# W040B.net
KiCad netlist of a schematic drawn in EAGLE
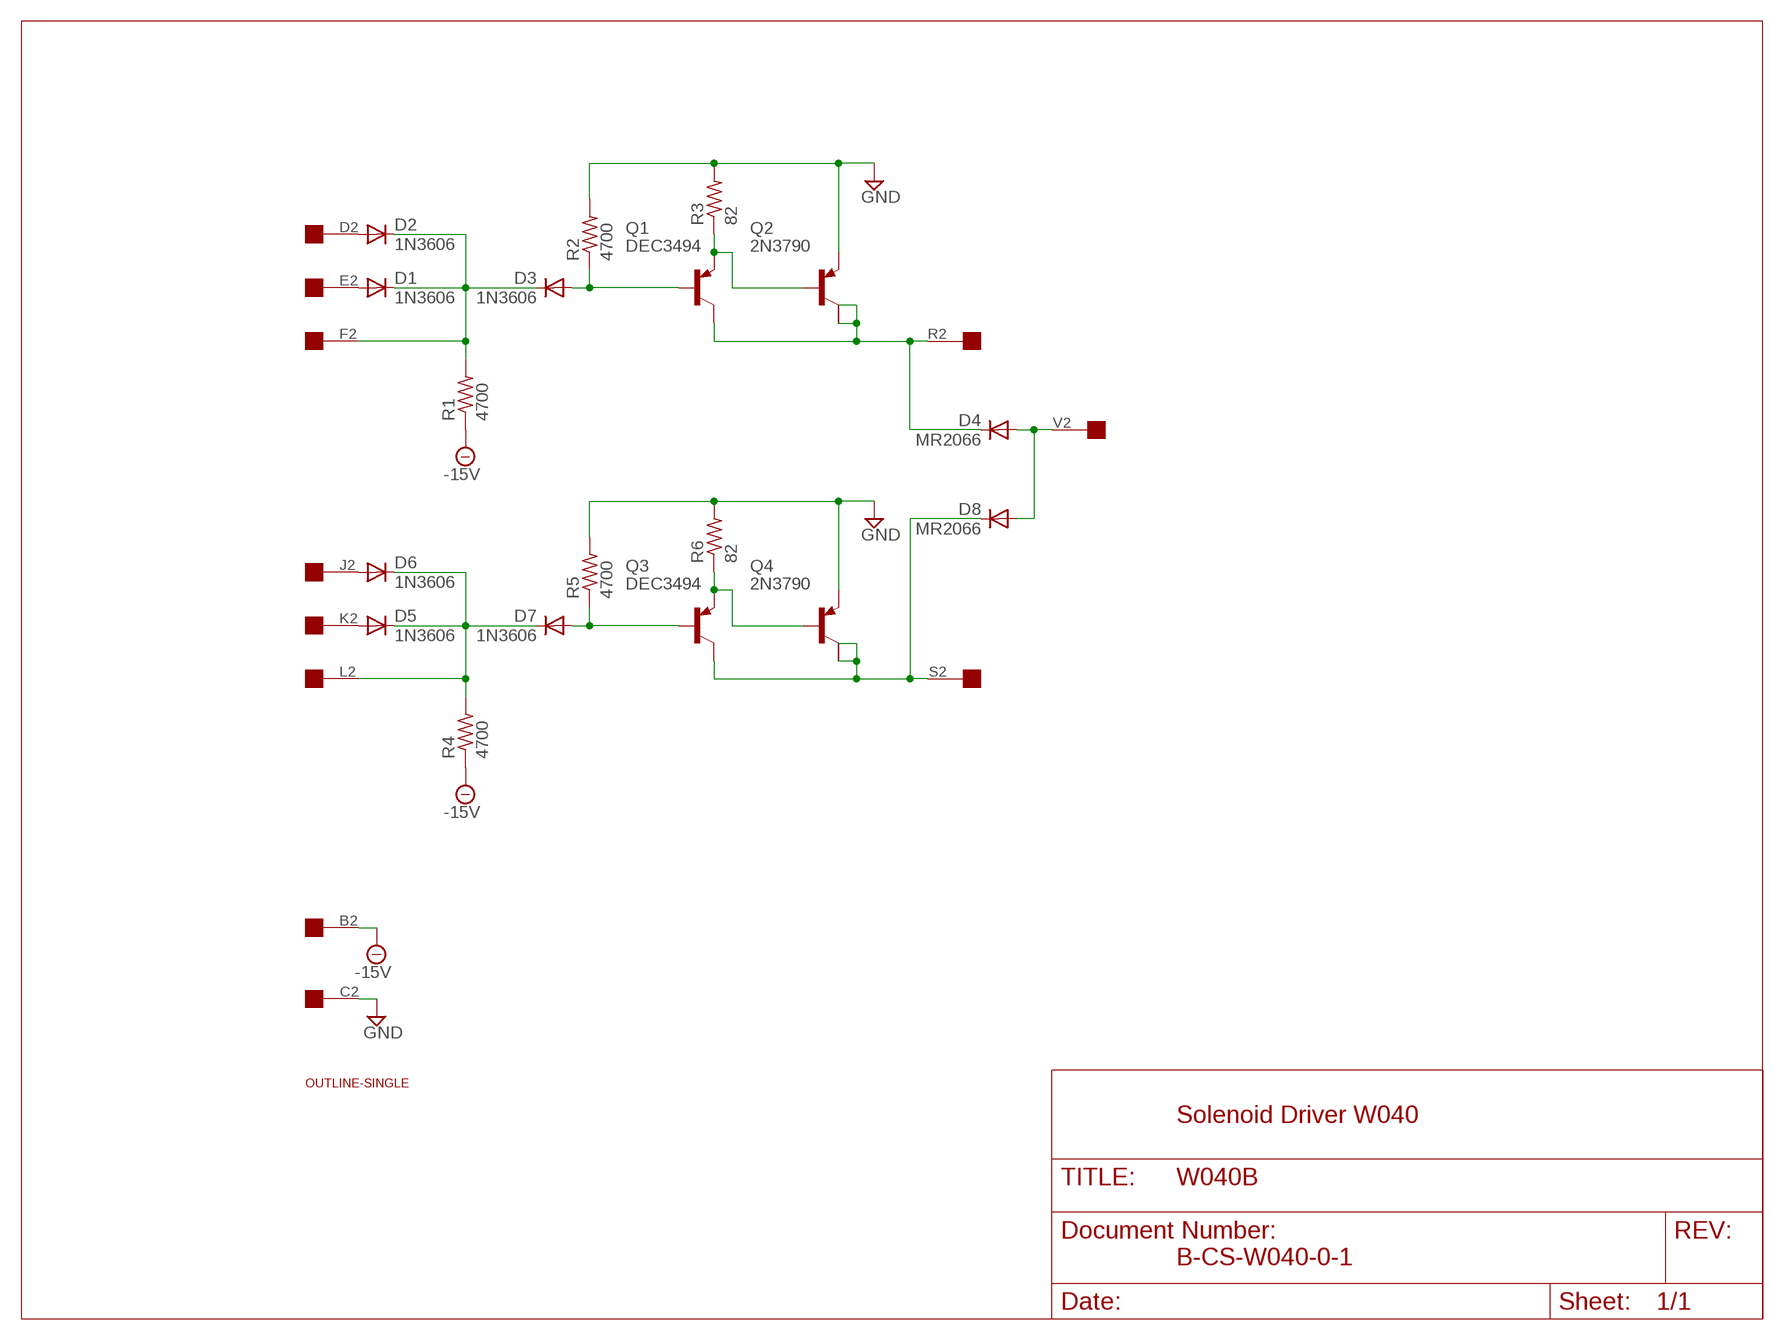
[diagram p0: schematic, sheet 1]

(export (version "E")
  (design (tool "Eeschema 10.0.6"))
  (components
    (comp (ref "D1")
      (value "1N3606")
      (footprint "eagle-import:DO35-10")
      (libsource (lib "eagle-import") (part "1N4148"))
    )
    (comp (ref "D2")
      (value "1N3606")
      (footprint "eagle-import:DO35-10")
      (libsource (lib "eagle-import") (part "1N4148"))
    )
    (comp (ref "D3")
      (value "1N3606")
      (footprint "eagle-import:DO35-10")
      (libsource (lib "eagle-import") (part "1N4148"))
    )
    (comp (ref "D4")
      (value "MR2066")
      (footprint "eagle-import:DO41-10")
      (libsource (lib "eagle-import") (part "1N4004"))
    )
    (comp (ref "D5")
      (value "1N3606")
      (footprint "eagle-import:DO35-10")
      (libsource (lib "eagle-import") (part "1N4148"))
    )
    (comp (ref "D6")
      (value "1N3606")
      (footprint "eagle-import:DO35-10")
      (libsource (lib "eagle-import") (part "1N4148"))
    )
    (comp (ref "D7")
      (value "1N3606")
      (footprint "eagle-import:DO35-10")
      (libsource (lib "eagle-import") (part "1N4148"))
    )
    (comp (ref "D8")
      (value "MR2066")
      (footprint "eagle-import:DO41-10")
      (libsource (lib "eagle-import") (part "1N4004"))
    )
    (comp (ref "Q1")
      (value "DEC3494")
      (footprint "eagle-import:TO39")
      (libsource (lib "eagle-import") (part "2N2904"))
    )
    (comp (ref "Q2")
      (value "2N3790")
      (footprint "eagle-import:TO3")
      (libsource (lib "eagle-import") (part "2N4902"))
    )
    (comp (ref "Q3")
      (value "DEC3494")
      (footprint "eagle-import:TO39")
      (libsource (lib "eagle-import") (part "2N2904"))
    )
    (comp (ref "Q4")
      (value "2N3790")
      (footprint "eagle-import:TO3")
      (libsource (lib "eagle-import") (part "2N4902"))
    )
    (comp (ref "R1")
      (value "4700")
      (footprint "eagle-import:0207_10")
      (libsource (lib "eagle-import") (part "R-US_0207/10"))
    )
    (comp (ref "R2")
      (value "4700")
      (footprint "eagle-import:0207_10")
      (libsource (lib "eagle-import") (part "R-US_0207/10"))
    )
    (comp (ref "R3")
      (value "82")
      (footprint "eagle-import:0207_10")
      (libsource (lib "eagle-import") (part "R-US_0207/10"))
    )
    (comp (ref "R4")
      (value "4700")
      (footprint "eagle-import:0207_10")
      (libsource (lib "eagle-import") (part "R-US_0207/10"))
    )
    (comp (ref "R5")
      (value "4700")
      (footprint "eagle-import:0207_10")
      (libsource (lib "eagle-import") (part "R-US_0207/10"))
    )
    (comp (ref "R6")
      (value "82")
      (footprint "eagle-import:0207_10")
      (libsource (lib "eagle-import") (part "R-US_0207/10"))
    )
    (comp (ref "U$1")
      (value "OUTLINE-SINGLE")
      (footprint "eagle-import:SINGLE")
      (libsource (lib "eagle-import") (part "OUTLINE-SINGLE"))
    )
    (comp (ref "U$2")
      (value "EDGE-1")
      (footprint "eagle-import:EDGE-CON1")
      (libsource (lib "eagle-import") (part "EDGE-1"))
    )
  )
  (nets
    (net (code "1") (name "-15V") (class "Default")
      (node (ref "R1") (pin "1") (pinfunction "1_1") (pintype "passive"))
      (node (ref "R4") (pin "1") (pinfunction "1_1") (pintype "passive"))
      (node (ref "U$2") (pin "B2") (pinfunction "1_B2") (pintype "bidirectional"))
    )
    (net (code "2") (name "GND") (class "Default")
      (node (ref "Q2") (pin "E") (pinfunction "E_E") (pintype "passive"))
      (node (ref "Q4") (pin "E") (pinfunction "E_E") (pintype "passive"))
      (node (ref "R2") (pin "2") (pinfunction "2_2") (pintype "passive"))
      (node (ref "R3") (pin "2") (pinfunction "2_2") (pintype "passive"))
      (node (ref "R5") (pin "2") (pinfunction "2_2") (pintype "passive"))
      (node (ref "R6") (pin "2") (pinfunction "2_2") (pintype "passive"))
      (node (ref "U$2") (pin "C2") (pinfunction "1_C2") (pintype "bidirectional"))
    )
    (net (code "3") (name "Net-(Q1-B)") (class "Default")
      (node (ref "D3") (pin "A") (pinfunction "A_A") (pintype "passive"))
      (node (ref "Q1") (pin "2") (pinfunction "B_2") (pintype "passive"))
      (node (ref "R2") (pin "1") (pinfunction "1_1") (pintype "passive"))
    )
    (net (code "4") (name "Net-(Q1-C)") (class "Default")
      (node (ref "D4") (pin "C") (pinfunction "C_C") (pintype "passive"))
      (node (ref "Q1") (pin "3") (pinfunction "C_3") (pintype "passive"))
      (node (ref "Q2") (pin "C") (pinfunction "C_C") (pintype "passive"))
      (node (ref "Q2") (pin "C/") (pinfunction "C/_C/") (pintype "passive"))
      (node (ref "U$2") (pin "R2") (pinfunction "1_R2") (pintype "bidirectional"))
    )
    (net (code "5") (name "Net-(Q1-E)") (class "Default")
      (node (ref "Q1") (pin "1") (pinfunction "E_1") (pintype "passive"))
      (node (ref "Q2") (pin "B") (pinfunction "B_B") (pintype "passive"))
      (node (ref "R3") (pin "1") (pinfunction "1_1") (pintype "passive"))
    )
    (net (code "6") (name "Net-(Q3-B)") (class "Default")
      (node (ref "D7") (pin "A") (pinfunction "A_A") (pintype "passive"))
      (node (ref "Q3") (pin "2") (pinfunction "B_2") (pintype "passive"))
      (node (ref "R5") (pin "1") (pinfunction "1_1") (pintype "passive"))
    )
    (net (code "7") (name "Net-(Q3-C)") (class "Default")
      (node (ref "D8") (pin "C") (pinfunction "C_C") (pintype "passive"))
      (node (ref "Q3") (pin "3") (pinfunction "C_3") (pintype "passive"))
      (node (ref "Q4") (pin "C") (pinfunction "C_C") (pintype "passive"))
      (node (ref "Q4") (pin "C/") (pinfunction "C/_C/") (pintype "passive"))
      (node (ref "U$2") (pin "S2") (pinfunction "1_S2") (pintype "bidirectional"))
    )
    (net (code "8") (name "Net-(Q3-E)") (class "Default")
      (node (ref "Q3") (pin "1") (pinfunction "E_1") (pintype "passive"))
      (node (ref "Q4") (pin "B") (pinfunction "B_B") (pintype "passive"))
      (node (ref "R6") (pin "1") (pinfunction "1_1") (pintype "passive"))
    )
    (net (code "9") (name "Net-(U$2D-1)") (class "Default")
      (node (ref "D2") (pin "A") (pinfunction "A_A") (pintype "passive"))
      (node (ref "U$2") (pin "D2") (pinfunction "1_D2") (pintype "bidirectional"))
    )
    (net (code "10") (name "Net-(U$2E-1)") (class "Default")
      (node (ref "D1") (pin "A") (pinfunction "A_A") (pintype "passive"))
      (node (ref "U$2") (pin "E2") (pinfunction "1_E2") (pintype "bidirectional"))
    )
    (net (code "11") (name "Net-(U$2F-1)") (class "Default")
      (node (ref "D1") (pin "C") (pinfunction "C_C") (pintype "passive"))
      (node (ref "D2") (pin "C") (pinfunction "C_C") (pintype "passive"))
      (node (ref "D3") (pin "C") (pinfunction "C_C") (pintype "passive"))
      (node (ref "R1") (pin "2") (pinfunction "2_2") (pintype "passive"))
      (node (ref "U$2") (pin "F2") (pinfunction "1_F2") (pintype "bidirectional"))
    )
    (net (code "12") (name "Net-(U$2H-1)") (class "Default")
      (node (ref "D6") (pin "A") (pinfunction "A_A") (pintype "passive"))
      (node (ref "U$2") (pin "J2") (pinfunction "1_J2") (pintype "bidirectional"))
    )
    (net (code "13") (name "Net-(U$2I-1)") (class "Default")
      (node (ref "D5") (pin "A") (pinfunction "A_A") (pintype "passive"))
      (node (ref "U$2") (pin "K2") (pinfunction "1_K2") (pintype "bidirectional"))
    )
    (net (code "14") (name "Net-(U$2J-1)") (class "Default")
      (node (ref "D5") (pin "C") (pinfunction "C_C") (pintype "passive"))
      (node (ref "D6") (pin "C") (pinfunction "C_C") (pintype "passive"))
      (node (ref "D7") (pin "C") (pinfunction "C_C") (pintype "passive"))
      (node (ref "R4") (pin "2") (pinfunction "2_2") (pintype "passive"))
      (node (ref "U$2") (pin "L2") (pinfunction "1_L2") (pintype "bidirectional"))
    )
    (net (code "15") (name "Net-(U$2R-1)") (class "Default")
      (node (ref "D4") (pin "A") (pinfunction "A_A") (pintype "passive"))
      (node (ref "D8") (pin "A") (pinfunction "A_A") (pintype "passive"))
      (node (ref "U$2") (pin "V2") (pinfunction "1_V2") (pintype "bidirectional"))
    )
  )
)
